# FRDM-Shield-Rev2_1.net
KiCad netlist of a schematic drawn in EAGLE
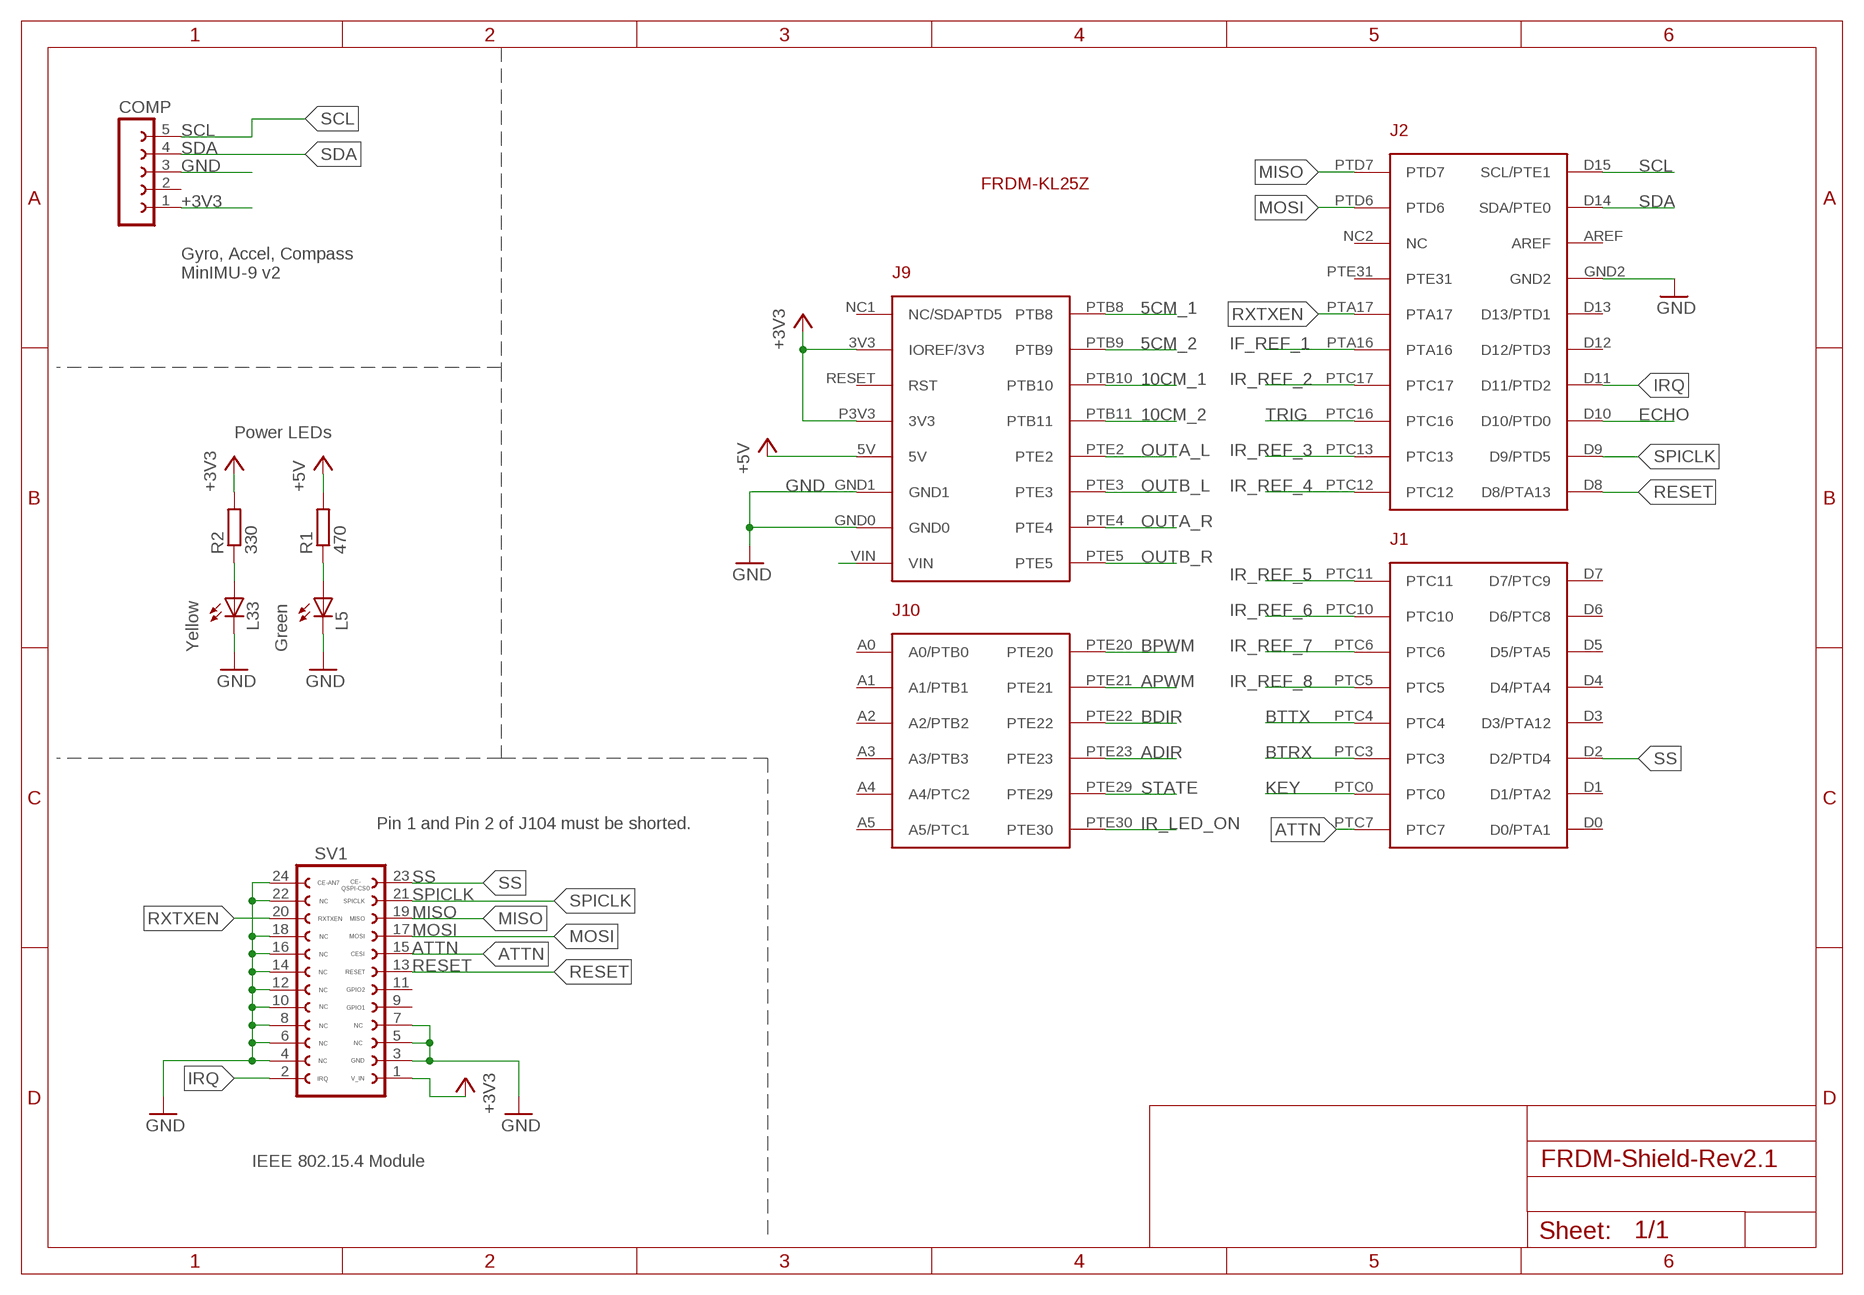
[diagram p0: schematic, sheet 1]

(export (version "E")
  (design (tool "Eeschema 10.0.6"))
  (components
    (comp (ref "COMP")
      (value "FE05-1")
      (footprint "eagle-import:FE05-1")
      (libsource (lib "eagle-import") (part "FE05-1"))
    )
    (comp (ref "FRDM1")
      (value "FRDM-KL25ZARDUINO")
      (footprint "eagle-import:FRDM-KL25Z")
      (libsource (lib "eagle-import") (part "FRDM-KL25ZARDUINO"))
    )
    (comp (ref "L5")
      (value "LEDCHIP-LED0603")
      (footprint "eagle-import:CHIP-LED0603")
      (libsource (lib "eagle-import") (part "LEDCHIP-LED0603"))
    )
    (comp (ref "L33")
      (value "LEDCHIP-LED0603")
      (footprint "eagle-import:CHIP-LED0603")
      (libsource (lib "eagle-import") (part "LEDCHIP-LED0603"))
    )
    (comp (ref "R1")
      (value "470")
      (footprint "eagle-import:M0805")
      (libsource (lib "eagle-import") (part "R-EU_M0805"))
    )
    (comp (ref "R2")
      (value "330")
      (footprint "eagle-import:M0805")
      (libsource (lib "eagle-import") (part "R-EU_M0805"))
    )
    (comp (ref "SV1")
      (value "MC1320X")
      (footprint "eagle-import:FE12-2")
      (libsource (lib "eagle-import") (part "MC1320X"))
    )
  )
  (nets
    (net (code "1") (name "+3V3") (class "Default")
      (node (ref "COMP") (pin "1") (pinfunction "1_1") (pintype "passive"))
      (node (ref "FRDM1") (pin "3V3") (pinfunction "IOREF/3V3_3V3") (pintype "bidirectional"))
      (node (ref "FRDM1") (pin "P3V3") (pinfunction "3V3_P3V3") (pintype "bidirectional"))
      (node (ref "R2") (pin "2") (pinfunction "2_2") (pintype "passive"))
      (node (ref "SV1") (pin "1") (pinfunction "1_1") (pintype "passive"))
    )
    (net (code "2") (name "+5V") (class "Default")
      (node (ref "FRDM1") (pin "5V") (pinfunction "5V_5V") (pintype "bidirectional"))
      (node (ref "R1") (pin "2") (pinfunction "2_2") (pintype "passive"))
    )
    (net (code "3") (name "/5CM_1") (class "Default")
      (node (ref "FRDM1") (pin "PTB8") (pinfunction "PTB8_PTB8") (pintype "bidirectional"))
    )
    (net (code "4") (name "/5CM_2") (class "Default")
      (node (ref "FRDM1") (pin "PTB9") (pinfunction "PTB9_PTB9") (pintype "bidirectional"))
    )
    (net (code "5") (name "/10CM_1") (class "Default")
      (node (ref "FRDM1") (pin "PTB10") (pinfunction "PTB10_PTB10") (pintype "bidirectional"))
    )
    (net (code "6") (name "/10CM_2") (class "Default")
      (node (ref "FRDM1") (pin "PTB11") (pinfunction "PTB11_PTB11") (pintype "bidirectional"))
    )
    (net (code "7") (name "/ADIR") (class "Default")
      (node (ref "FRDM1") (pin "PTE23") (pinfunction "PTE23_PTE23") (pintype "bidirectional"))
    )
    (net (code "8") (name "/APWM") (class "Default")
      (node (ref "FRDM1") (pin "PTE21") (pinfunction "PTE21_PTE21") (pintype "bidirectional"))
    )
    (net (code "9") (name "/BDIR") (class "Default")
      (node (ref "FRDM1") (pin "PTE22") (pinfunction "PTE22_PTE22") (pintype "bidirectional"))
    )
    (net (code "10") (name "/BPWM") (class "Default")
      (node (ref "FRDM1") (pin "PTE20") (pinfunction "PTE20_PTE20") (pintype "bidirectional"))
    )
    (net (code "11") (name "/BTRX") (class "Default")
      (node (ref "FRDM1") (pin "PTC3") (pinfunction "PTC3_PTC3") (pintype "bidirectional"))
    )
    (net (code "12") (name "/BTTX") (class "Default")
      (node (ref "FRDM1") (pin "PTC4") (pinfunction "PTC4_PTC4") (pintype "bidirectional"))
    )
    (net (code "13") (name "/ECHO") (class "Default")
      (node (ref "FRDM1") (pin "D10") (pinfunction "D10/PTD0_D10") (pintype "bidirectional"))
    )
    (net (code "14") (name "/IF_REF_1") (class "Default")
      (node (ref "FRDM1") (pin "PTA16") (pinfunction "PTA16_PTA16") (pintype "bidirectional"))
    )
    (net (code "15") (name "/IR_LED_ON") (class "Default")
      (node (ref "FRDM1") (pin "PTE30") (pinfunction "PTE30_PTE30") (pintype "bidirectional"))
    )
    (net (code "16") (name "/IR_REF_2") (class "Default")
      (node (ref "FRDM1") (pin "PTC17") (pinfunction "PTC17_PTC17") (pintype "bidirectional"))
    )
    (net (code "17") (name "/IR_REF_3") (class "Default")
      (node (ref "FRDM1") (pin "PTC13") (pinfunction "PTC13_PTC13") (pintype "bidirectional"))
    )
    (net (code "18") (name "/IR_REF_4") (class "Default")
      (node (ref "FRDM1") (pin "PTC12") (pinfunction "PTC12_PTC12") (pintype "bidirectional"))
    )
    (net (code "19") (name "/IR_REF_5") (class "Default")
      (node (ref "FRDM1") (pin "PTC11") (pinfunction "PTC11_PTC11") (pintype "bidirectional"))
    )
    (net (code "20") (name "/IR_REF_6") (class "Default")
      (node (ref "FRDM1") (pin "PTC10") (pinfunction "PTC10_PTC10") (pintype "bidirectional"))
    )
    (net (code "21") (name "/IR_REF_7") (class "Default")
      (node (ref "FRDM1") (pin "PTC6") (pinfunction "PTC6_PTC6") (pintype "bidirectional"))
    )
    (net (code "22") (name "/IR_REF_8") (class "Default")
      (node (ref "FRDM1") (pin "PTC5") (pinfunction "PTC5_PTC5") (pintype "bidirectional"))
    )
    (net (code "23") (name "/KEY") (class "Default")
      (node (ref "FRDM1") (pin "PTC0") (pinfunction "PTC0_PTC0") (pintype "bidirectional"))
    )
    (net (code "24") (name "/OUTA_L") (class "Default")
      (node (ref "FRDM1") (pin "PTE2") (pinfunction "PTE2_PTE2") (pintype "bidirectional"))
    )
    (net (code "25") (name "/OUTA_R") (class "Default")
      (node (ref "FRDM1") (pin "PTE4") (pinfunction "PTE4_PTE4") (pintype "bidirectional"))
    )
    (net (code "26") (name "/OUTB_L") (class "Default")
      (node (ref "FRDM1") (pin "PTE3") (pinfunction "PTE3_PTE3") (pintype "bidirectional"))
    )
    (net (code "27") (name "/OUTB_R") (class "Default")
      (node (ref "FRDM1") (pin "PTE5") (pinfunction "PTE5_PTE5") (pintype "bidirectional"))
    )
    (net (code "28") (name "/STATE") (class "Default")
      (node (ref "FRDM1") (pin "PTE29") (pinfunction "PTE29_PTE29") (pintype "bidirectional"))
    )
    (net (code "29") (name "/TRIG") (class "Default")
      (node (ref "FRDM1") (pin "PTC16") (pinfunction "PTC16_PTC16") (pintype "bidirectional"))
    )
    (net (code "30") (name "ATTN") (class "Default")
      (node (ref "FRDM1") (pin "PTC7") (pinfunction "PTC7_PTC7") (pintype "bidirectional"))
      (node (ref "SV1") (pin "15") (pinfunction "15_15") (pintype "passive"))
    )
    (net (code "31") (name "GND") (class "Default")
      (node (ref "COMP") (pin "3") (pinfunction "3_3") (pintype "passive"))
      (node (ref "FRDM1") (pin "GND0") (pinfunction "GND0_GND0") (pintype "bidirectional"))
      (node (ref "FRDM1") (pin "GND1") (pinfunction "GND1_GND1") (pintype "bidirectional"))
      (node (ref "FRDM1") (pin "GND2") (pinfunction "GND2_GND2") (pintype "bidirectional"))
      (node (ref "L33") (pin "C") (pinfunction "C_C") (pintype "passive"))
      (node (ref "L5") (pin "C") (pinfunction "C_C") (pintype "passive"))
      (node (ref "SV1") (pin "10") (pinfunction "10_10") (pintype "passive"))
      (node (ref "SV1") (pin "12") (pinfunction "12_12") (pintype "passive"))
      (node (ref "SV1") (pin "14") (pinfunction "14_14") (pintype "passive"))
      (node (ref "SV1") (pin "16") (pinfunction "16_16") (pintype "passive"))
      (node (ref "SV1") (pin "18") (pinfunction "18_18") (pintype "passive"))
      (node (ref "SV1") (pin "22") (pinfunction "22_22") (pintype "passive"))
      (node (ref "SV1") (pin "24") (pinfunction "24_24") (pintype "passive"))
      (node (ref "SV1") (pin "3") (pinfunction "3_3") (pintype "passive"))
      (node (ref "SV1") (pin "4") (pinfunction "4_4") (pintype "passive"))
      (node (ref "SV1") (pin "5") (pinfunction "5_5") (pintype "passive"))
      (node (ref "SV1") (pin "6") (pinfunction "6_6") (pintype "passive"))
      (node (ref "SV1") (pin "7") (pinfunction "7_7") (pintype "passive"))
      (node (ref "SV1") (pin "8") (pinfunction "8_8") (pintype "passive"))
    )
    (net (code "32") (name "IRQ") (class "Default")
      (node (ref "FRDM1") (pin "D11") (pinfunction "D11/PTD2_D11") (pintype "bidirectional"))
      (node (ref "SV1") (pin "2") (pinfunction "2_2") (pintype "passive"))
    )
    (net (code "33") (name "MISO") (class "Default")
      (node (ref "FRDM1") (pin "PTD7") (pinfunction "PTD7_PTD7") (pintype "bidirectional"))
      (node (ref "SV1") (pin "19") (pinfunction "19_19") (pintype "passive"))
    )
    (net (code "34") (name "MOSI") (class "Default")
      (node (ref "FRDM1") (pin "PTD6") (pinfunction "PTD6_PTD6") (pintype "bidirectional"))
      (node (ref "SV1") (pin "17") (pinfunction "17_17") (pintype "passive"))
    )
    (net (code "35") (name "Net-(L5-PadA)") (class "Default")
      (node (ref "L5") (pin "A") (pinfunction "A_A") (pintype "passive"))
      (node (ref "R1") (pin "1") (pinfunction "1_1") (pintype "passive"))
    )
    (net (code "36") (name "Net-(L33-PadA)") (class "Default")
      (node (ref "L33") (pin "A") (pinfunction "A_A") (pintype "passive"))
      (node (ref "R2") (pin "1") (pinfunction "1_1") (pintype "passive"))
    )
    (net (code "37") (name "RESET") (class "Default")
      (node (ref "FRDM1") (pin "D8") (pinfunction "D8/PTA13_D8") (pintype "bidirectional"))
      (node (ref "SV1") (pin "13") (pinfunction "13_13") (pintype "passive"))
    )
    (net (code "38") (name "RXTXEN") (class "Default")
      (node (ref "FRDM1") (pin "PTA17") (pinfunction "PTA17_PTA17") (pintype "bidirectional"))
      (node (ref "SV1") (pin "20") (pinfunction "20_20") (pintype "passive"))
    )
    (net (code "39") (name "SCL") (class "Default")
      (node (ref "COMP") (pin "5") (pinfunction "5_5") (pintype "passive"))
      (node (ref "FRDM1") (pin "D15") (pinfunction "SCL/PTE1_D15") (pintype "bidirectional"))
    )
    (net (code "40") (name "SDA") (class "Default")
      (node (ref "COMP") (pin "4") (pinfunction "4_4") (pintype "passive"))
      (node (ref "FRDM1") (pin "D14") (pinfunction "SDA/PTE0_D14") (pintype "bidirectional"))
    )
    (net (code "41") (name "SPICLK") (class "Default")
      (node (ref "FRDM1") (pin "D9") (pinfunction "D9/PTD5_D9") (pintype "bidirectional"))
      (node (ref "SV1") (pin "21") (pinfunction "21_21") (pintype "passive"))
    )
    (net (code "42") (name "SS") (class "Default")
      (node (ref "FRDM1") (pin "D2") (pinfunction "D2/PTD4_D2") (pintype "bidirectional"))
      (node (ref "SV1") (pin "23") (pinfunction "23_23") (pintype "passive"))
    )
    (net (code "43") (name "unconnected-(COMP-Pad2)") (class "Default")
      (node (ref "COMP") (pin "2") (pinfunction "2_2") (pintype "passive"))
    )
    (net (code "44") (name "unconnected-(FRDM1-A0{slash}PTB0-PadA0)") (class "Default")
      (node (ref "FRDM1") (pin "A0") (pinfunction "A0/PTB0_A0") (pintype "bidirectional"))
    )
    (net (code "45") (name "unconnected-(FRDM1-A1{slash}PTB1-PadA1)") (class "Default")
      (node (ref "FRDM1") (pin "A1") (pinfunction "A1/PTB1_A1") (pintype "bidirectional"))
    )
    (net (code "46") (name "unconnected-(FRDM1-A2{slash}PTB2-PadA2)") (class "Default")
      (node (ref "FRDM1") (pin "A2") (pinfunction "A2/PTB2_A2") (pintype "bidirectional"))
    )
    (net (code "47") (name "unconnected-(FRDM1-A3{slash}PTB3-PadA3)") (class "Default")
      (node (ref "FRDM1") (pin "A3") (pinfunction "A3/PTB3_A3") (pintype "bidirectional"))
    )
    (net (code "48") (name "unconnected-(FRDM1-A4{slash}PTC2-PadA4)") (class "Default")
      (node (ref "FRDM1") (pin "A4") (pinfunction "A4/PTC2_A4") (pintype "bidirectional"))
    )
    (net (code "49") (name "unconnected-(FRDM1-A5{slash}PTC1-PadA5)") (class "Default")
      (node (ref "FRDM1") (pin "A5") (pinfunction "A5/PTC1_A5") (pintype "bidirectional"))
    )
    (net (code "50") (name "unconnected-(FRDM1-D0{slash}PTA1-PadD0)") (class "Default")
      (node (ref "FRDM1") (pin "D0") (pinfunction "D0/PTA1_D0") (pintype "bidirectional"))
    )
    (net (code "51") (name "unconnected-(FRDM1-D1{slash}PTA2-PadD1)") (class "Default")
      (node (ref "FRDM1") (pin "D1") (pinfunction "D1/PTA2_D1") (pintype "bidirectional"))
    )
    (net (code "52") (name "unconnected-(FRDM1-D3{slash}PTA12-PadD3)") (class "Default")
      (node (ref "FRDM1") (pin "D3") (pinfunction "D3/PTA12_D3") (pintype "bidirectional"))
    )
    (net (code "53") (name "unconnected-(FRDM1-D4{slash}PTA4-PadD4)") (class "Default")
      (node (ref "FRDM1") (pin "D4") (pinfunction "D4/PTA4_D4") (pintype "bidirectional"))
    )
    (net (code "54") (name "unconnected-(FRDM1-D5{slash}PTA5-PadD5)") (class "Default")
      (node (ref "FRDM1") (pin "D5") (pinfunction "D5/PTA5_D5") (pintype "bidirectional"))
    )
    (net (code "55") (name "unconnected-(FRDM1-D6{slash}PTC8-PadD6)") (class "Default")
      (node (ref "FRDM1") (pin "D6") (pinfunction "D6/PTC8_D6") (pintype "bidirectional"))
    )
    (net (code "56") (name "unconnected-(FRDM1-D7{slash}PTC9-PadD7)") (class "Default")
      (node (ref "FRDM1") (pin "D7") (pinfunction "D7/PTC9_D7") (pintype "bidirectional"))
    )
    (net (code "57") (name "unconnected-(FRDM1-D12{slash}PTD3-PadD12)") (class "Default")
      (node (ref "FRDM1") (pin "D12") (pinfunction "D12/PTD3_D12") (pintype "bidirectional"))
    )
    (net (code "58") (name "unconnected-(FRDM1-D13{slash}PTD1-PadD13)") (class "Default")
      (node (ref "FRDM1") (pin "D13") (pinfunction "D13/PTD1_D13") (pintype "bidirectional"))
    )
    (net (code "59") (name "unconnected-(FRDM1-NC-PadNC2)") (class "Default")
      (node (ref "FRDM1") (pin "NC2") (pinfunction "NC_NC2") (pintype "bidirectional"))
    )
    (net (code "60") (name "unconnected-(FRDM1-NC{slash}SDAPTD5-PadNC1)") (class "Default")
      (node (ref "FRDM1") (pin "NC1") (pinfunction "NC/SDAPTD5_NC1") (pintype "bidirectional"))
    )
    (net (code "61") (name "unconnected-(FRDM1-PadAREF)") (class "Default")
      (node (ref "FRDM1") (pin "AREF") (pinfunction "AREF_AREF") (pintype "bidirectional"))
    )
    (net (code "62") (name "unconnected-(FRDM1-PadPTE31)") (class "Default")
      (node (ref "FRDM1") (pin "PTE31") (pinfunction "PTE31_PTE31") (pintype "bidirectional"))
    )
    (net (code "63") (name "unconnected-(FRDM1-PadVIN)") (class "Default")
      (node (ref "FRDM1") (pin "VIN") (pinfunction "VIN_VIN") (pintype "bidirectional"))
    )
    (net (code "64") (name "unconnected-(FRDM1-RST-PadRESET)") (class "Default")
      (node (ref "FRDM1") (pin "RESET") (pinfunction "RST_RESET") (pintype "bidirectional"))
    )
    (net (code "65") (name "unconnected-(SV1-Pad9)") (class "Default")
      (node (ref "SV1") (pin "9") (pinfunction "9_9") (pintype "passive"))
    )
    (net (code "66") (name "unconnected-(SV1-Pad11)") (class "Default")
      (node (ref "SV1") (pin "11") (pinfunction "11_11") (pintype "passive"))
    )
  )
)
